# 03_CORE_BOARD.net
KiCad netlist of a schematic drawn in Altium Designer
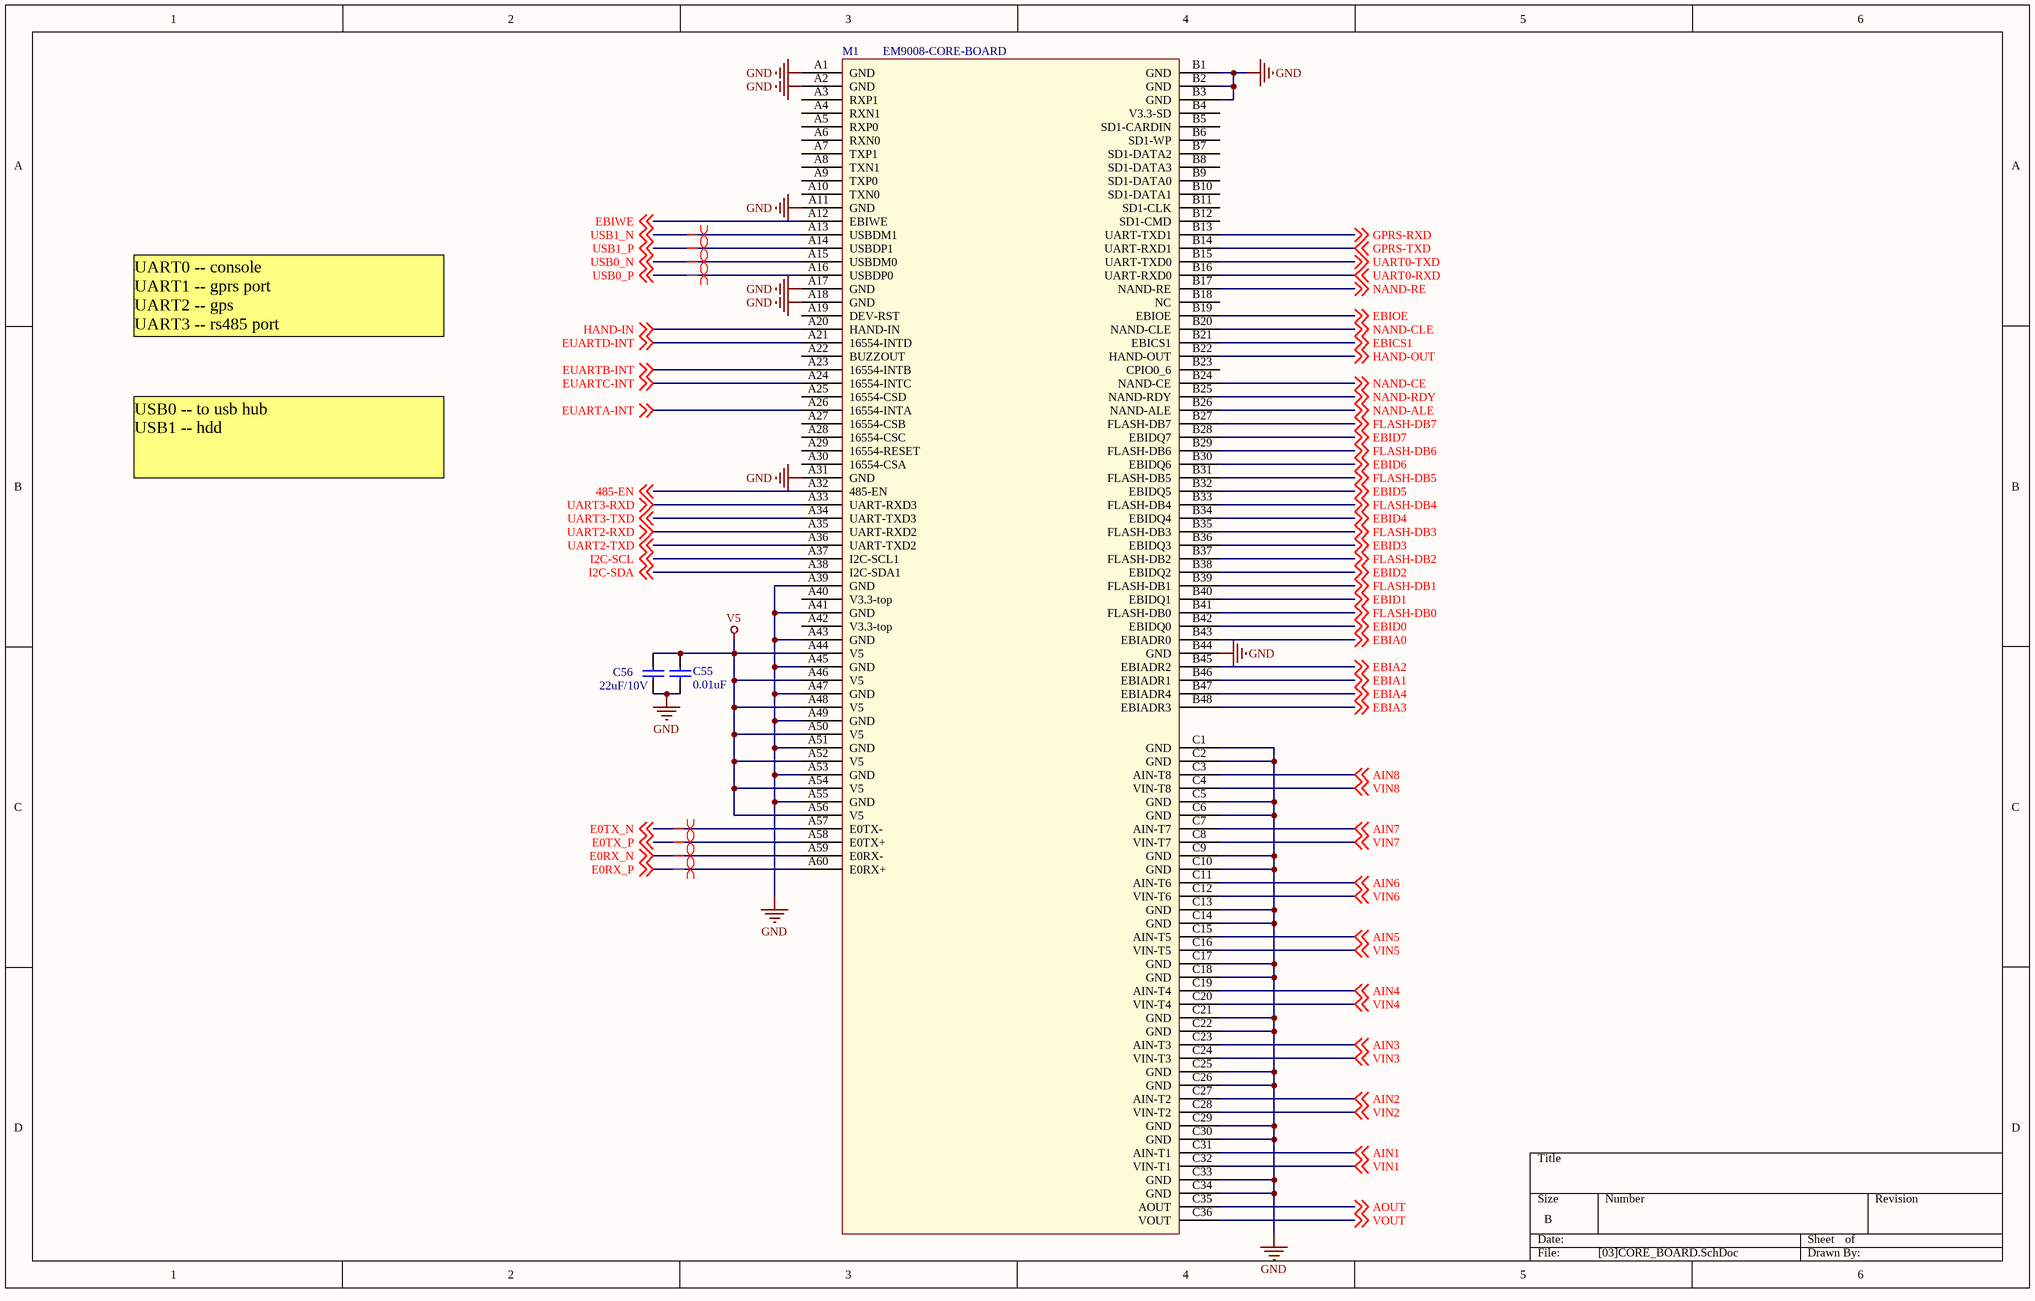
[diagram p0: [03]CORE_BOARD.SchDoc]

(export (version "E")
  (design (tool "Eeschema 10.0.6"))
  (components
    (comp (ref "C55")
      (value "0.01uF")
      (footprint "0603")
      (description "Capacitor")
      (libsource (lib "Miscellaneous Devices") (part "Cap"))
    )
    (comp (ref "C56")
      (value "22uF/10V")
      (footprint "1210")
      (description "Capacitor")
      (libsource (lib "Miscellaneous Devices") (part "Cap"))
    )
    (comp (ref "M1")
      (value "EM9008-CORE-BOARD")
      (footprint "EM9008")
      (libsource (lib "Schlib") (part "EM9008-CORE-BOARD"))
    )
  )
  (nets
    (net (code "1") (name "485-EN") (class "Default")
      (node (ref "M1") (pin "A32") (pinfunction "485-EN_A32") (pintype "passive"))
    )
    (net (code "2") (name "AIN1") (class "Default")
      (node (ref "M1") (pin "C31") (pinfunction "AIN-T1_C31") (pintype "passive"))
    )
    (net (code "3") (name "AIN2") (class "Default")
      (node (ref "M1") (pin "C27") (pinfunction "AIN-T2_C27") (pintype "passive"))
    )
    (net (code "4") (name "AIN3") (class "Default")
      (node (ref "M1") (pin "C23") (pinfunction "AIN-T3_C23") (pintype "passive"))
    )
    (net (code "5") (name "AIN4") (class "Default")
      (node (ref "M1") (pin "C19") (pinfunction "AIN-T4_C19") (pintype "passive"))
    )
    (net (code "6") (name "AIN5") (class "Default")
      (node (ref "M1") (pin "C15") (pinfunction "AIN-T5_C15") (pintype "passive"))
    )
    (net (code "7") (name "AIN6") (class "Default")
      (node (ref "M1") (pin "C11") (pinfunction "AIN-T6_C11") (pintype "passive"))
    )
    (net (code "8") (name "AIN7") (class "Default")
      (node (ref "M1") (pin "C7") (pinfunction "AIN-T7_C7") (pintype "passive"))
    )
    (net (code "9") (name "AIN8") (class "Default")
      (node (ref "M1") (pin "C3") (pinfunction "AIN-T8_C3") (pintype "passive"))
    )
    (net (code "10") (name "AOUT") (class "Default")
      (node (ref "M1") (pin "C35") (pinfunction "AOUT_C35") (pintype "passive"))
    )
    (net (code "11") (name "E0RX_N") (class "Default")
      (node (ref "M1") (pin "A59") (pinfunction "E0RX-_A59") (pintype "passive"))
    )
    (net (code "12") (name "E0RX_P") (class "Default")
      (node (ref "M1") (pin "A60") (pinfunction "E0RX+_A60") (pintype "passive"))
    )
    (net (code "13") (name "E0TX_N") (class "Default")
      (node (ref "M1") (pin "A57") (pinfunction "E0TX-_A57") (pintype "passive"))
    )
    (net (code "14") (name "E0TX_P") (class "Default")
      (node (ref "M1") (pin "A58") (pinfunction "E0TX+_A58") (pintype "passive"))
    )
    (net (code "15") (name "EBIA0") (class "Default")
      (node (ref "M1") (pin "B43") (pinfunction "EBIADR0_B43") (pintype "passive"))
    )
    (net (code "16") (name "EBIA1") (class "Default")
      (node (ref "M1") (pin "B46") (pinfunction "EBIADR1_B46") (pintype "passive"))
    )
    (net (code "17") (name "EBIA2") (class "Default")
      (node (ref "M1") (pin "B45") (pinfunction "EBIADR2_B45") (pintype "passive"))
    )
    (net (code "18") (name "EBIA3") (class "Default")
      (node (ref "M1") (pin "B48") (pinfunction "EBIADR3_B48") (pintype "passive"))
    )
    (net (code "19") (name "EBIA4") (class "Default")
      (node (ref "M1") (pin "B47") (pinfunction "EBIADR4_B47") (pintype "passive"))
    )
    (net (code "20") (name "EBICS1") (class "Default")
      (node (ref "M1") (pin "B21") (pinfunction "EBICS1_B21") (pintype "passive"))
    )
    (net (code "21") (name "EBID0") (class "Default")
      (node (ref "M1") (pin "B42") (pinfunction "EBIDQ0_B42") (pintype "passive"))
    )
    (net (code "22") (name "EBID1") (class "Default")
      (node (ref "M1") (pin "B40") (pinfunction "EBIDQ1_B40") (pintype "passive"))
    )
    (net (code "23") (name "EBID2") (class "Default")
      (node (ref "M1") (pin "B38") (pinfunction "EBIDQ2_B38") (pintype "passive"))
    )
    (net (code "24") (name "EBID3") (class "Default")
      (node (ref "M1") (pin "B36") (pinfunction "EBIDQ3_B36") (pintype "passive"))
    )
    (net (code "25") (name "EBID4") (class "Default")
      (node (ref "M1") (pin "B34") (pinfunction "EBIDQ4_B34") (pintype "passive"))
    )
    (net (code "26") (name "EBID5") (class "Default")
      (node (ref "M1") (pin "B32") (pinfunction "EBIDQ5_B32") (pintype "passive"))
    )
    (net (code "27") (name "EBID6") (class "Default")
      (node (ref "M1") (pin "B30") (pinfunction "EBIDQ6_B30") (pintype "passive"))
    )
    (net (code "28") (name "EBID7") (class "Default")
      (node (ref "M1") (pin "B28") (pinfunction "EBIDQ7_B28") (pintype "passive"))
    )
    (net (code "29") (name "EBIOE") (class "Default")
      (node (ref "M1") (pin "B19") (pinfunction "EBIOE_B19") (pintype "passive"))
    )
    (net (code "30") (name "EBIWE") (class "Default")
      (node (ref "M1") (pin "A12") (pinfunction "EBIWE_A12") (pintype "passive"))
    )
    (net (code "31") (name "EUARTA-INT") (class "Default")
      (node (ref "M1") (pin "A26") (pinfunction "16554-INTA_A26") (pintype "passive"))
    )
    (net (code "32") (name "EUARTB-INT") (class "Default")
      (node (ref "M1") (pin "A23") (pinfunction "16554-INTB_A23") (pintype "passive"))
    )
    (net (code "33") (name "EUARTC-INT") (class "Default")
      (node (ref "M1") (pin "A24") (pinfunction "16554-INTC_A24") (pintype "passive"))
    )
    (net (code "34") (name "EUARTD-INT") (class "Default")
      (node (ref "M1") (pin "A21") (pinfunction "16554-INTD_A21") (pintype "passive"))
    )
    (net (code "35") (name "FLASH-DB0") (class "Default")
      (node (ref "M1") (pin "B41") (pinfunction "FLASH-DB0_B41") (pintype "passive"))
    )
    (net (code "36") (name "FLASH-DB1") (class "Default")
      (node (ref "M1") (pin "B39") (pinfunction "FLASH-DB1_B39") (pintype "passive"))
    )
    (net (code "37") (name "FLASH-DB2") (class "Default")
      (node (ref "M1") (pin "B37") (pinfunction "FLASH-DB2_B37") (pintype "passive"))
    )
    (net (code "38") (name "FLASH-DB3") (class "Default")
      (node (ref "M1") (pin "B35") (pinfunction "FLASH-DB3_B35") (pintype "passive"))
    )
    (net (code "39") (name "FLASH-DB4") (class "Default")
      (node (ref "M1") (pin "B33") (pinfunction "FLASH-DB4_B33") (pintype "passive"))
    )
    (net (code "40") (name "FLASH-DB5") (class "Default")
      (node (ref "M1") (pin "B31") (pinfunction "FLASH-DB5_B31") (pintype "passive"))
    )
    (net (code "41") (name "FLASH-DB6") (class "Default")
      (node (ref "M1") (pin "B29") (pinfunction "FLASH-DB6_B29") (pintype "passive"))
    )
    (net (code "42") (name "FLASH-DB7") (class "Default")
      (node (ref "M1") (pin "B27") (pinfunction "FLASH-DB7_B27") (pintype "passive"))
    )
    (net (code "43") (name "GND") (class "Default")
      (node (ref "C55") (pin "1") (pinfunction "1_1") (pintype "passive"))
      (node (ref "C56") (pin "1") (pinfunction "1_1") (pintype "passive"))
      (node (ref "M1") (pin "A1") (pinfunction "GND_A1") (pintype "passive"))
      (node (ref "M1") (pin "A11") (pinfunction "GND_A11") (pintype "passive"))
      (node (ref "M1") (pin "A17") (pinfunction "GND_A17") (pintype "passive"))
      (node (ref "M1") (pin "A18") (pinfunction "GND_A18") (pintype "passive"))
      (node (ref "M1") (pin "A2") (pinfunction "GND_A2") (pintype "passive"))
      (node (ref "M1") (pin "A31") (pinfunction "GND_A31") (pintype "passive"))
      (node (ref "M1") (pin "A39") (pinfunction "GND_A39") (pintype "passive"))
      (node (ref "M1") (pin "A41") (pinfunction "GND_A41") (pintype "passive"))
      (node (ref "M1") (pin "A43") (pinfunction "GND_A43") (pintype "passive"))
      (node (ref "M1") (pin "A45") (pinfunction "GND_A45") (pintype "passive"))
      (node (ref "M1") (pin "A47") (pinfunction "GND_A47") (pintype "passive"))
      (node (ref "M1") (pin "A49") (pinfunction "GND_A49") (pintype "passive"))
      (node (ref "M1") (pin "A51") (pinfunction "GND_A51") (pintype "passive"))
      (node (ref "M1") (pin "A53") (pinfunction "GND_A53") (pintype "passive"))
      (node (ref "M1") (pin "A55") (pinfunction "GND_A55") (pintype "passive"))
      (node (ref "M1") (pin "B1") (pinfunction "GND_B1") (pintype "passive"))
      (node (ref "M1") (pin "B2") (pinfunction "GND_B2") (pintype "passive"))
      (node (ref "M1") (pin "B3") (pinfunction "GND_B3") (pintype "passive"))
      (node (ref "M1") (pin "B44") (pinfunction "GND_B44") (pintype "passive"))
      (node (ref "M1") (pin "C1") (pinfunction "GND_C1") (pintype "passive"))
      (node (ref "M1") (pin "C10") (pinfunction "GND_C10") (pintype "passive"))
      (node (ref "M1") (pin "C13") (pinfunction "GND_C13") (pintype "passive"))
      (node (ref "M1") (pin "C14") (pinfunction "GND_C14") (pintype "passive"))
      (node (ref "M1") (pin "C17") (pinfunction "GND_C17") (pintype "passive"))
      (node (ref "M1") (pin "C18") (pinfunction "GND_C18") (pintype "passive"))
      (node (ref "M1") (pin "C2") (pinfunction "GND_C2") (pintype "passive"))
      (node (ref "M1") (pin "C21") (pinfunction "GND_C21") (pintype "passive"))
      (node (ref "M1") (pin "C22") (pinfunction "GND_C22") (pintype "passive"))
      (node (ref "M1") (pin "C25") (pinfunction "GND_C25") (pintype "passive"))
      (node (ref "M1") (pin "C26") (pinfunction "GND_C26") (pintype "passive"))
      (node (ref "M1") (pin "C29") (pinfunction "GND_C29") (pintype "passive"))
      (node (ref "M1") (pin "C30") (pinfunction "GND_C30") (pintype "passive"))
      (node (ref "M1") (pin "C33") (pinfunction "GND_C33") (pintype "passive"))
      (node (ref "M1") (pin "C34") (pinfunction "GND_C34") (pintype "passive"))
      (node (ref "M1") (pin "C5") (pinfunction "GND_C5") (pintype "passive"))
      (node (ref "M1") (pin "C6") (pinfunction "GND_C6") (pintype "passive"))
      (node (ref "M1") (pin "C9") (pinfunction "GND_C9") (pintype "passive"))
    )
    (net (code "44") (name "GPRS-RXD") (class "Default")
      (node (ref "M1") (pin "B13") (pinfunction "UART-TXD1_B13") (pintype "passive"))
    )
    (net (code "45") (name "GPRS-TXD") (class "Default")
      (node (ref "M1") (pin "B14") (pinfunction "UART-RXD1_B14") (pintype "passive"))
    )
    (net (code "46") (name "HAND-IN") (class "Default")
      (node (ref "M1") (pin "A20") (pinfunction "HAND-IN_A20") (pintype "passive"))
    )
    (net (code "47") (name "HAND-OUT") (class "Default")
      (node (ref "M1") (pin "B22") (pinfunction "HAND-OUT_B22") (pintype "passive"))
    )
    (net (code "48") (name "I2C-SCL") (class "Default")
      (node (ref "M1") (pin "A37") (pinfunction "I2C-SCL1_A37") (pintype "passive"))
    )
    (net (code "49") (name "I2C-SDA") (class "Default")
      (node (ref "M1") (pin "A38") (pinfunction "I2C-SDA1_A38") (pintype "passive"))
    )
    (net (code "50") (name "NAND-ALE") (class "Default")
      (node (ref "M1") (pin "B26") (pinfunction "NAND-ALE_B26") (pintype "passive"))
    )
    (net (code "51") (name "NAND-CE") (class "Default")
      (node (ref "M1") (pin "B24") (pinfunction "NAND-CE_B24") (pintype "passive"))
    )
    (net (code "52") (name "NAND-CLE") (class "Default")
      (node (ref "M1") (pin "B20") (pinfunction "NAND-CLE_B20") (pintype "passive"))
    )
    (net (code "53") (name "NAND-RDY") (class "Default")
      (node (ref "M1") (pin "B25") (pinfunction "NAND-RDY_B25") (pintype "passive"))
    )
    (net (code "54") (name "NAND-RE") (class "Default")
      (node (ref "M1") (pin "B17") (pinfunction "NAND-RE_B17") (pintype "passive"))
    )
    (net (code "55") (name "UART0-RXD") (class "Default")
      (node (ref "M1") (pin "B16") (pinfunction "UART-RXD0_B16") (pintype "passive"))
    )
    (net (code "56") (name "UART0-TXD") (class "Default")
      (node (ref "M1") (pin "B15") (pinfunction "UART-TXD0_B15") (pintype "passive"))
    )
    (net (code "57") (name "UART2-RXD") (class "Default")
      (node (ref "M1") (pin "A35") (pinfunction "UART-RXD2_A35") (pintype "passive"))
    )
    (net (code "58") (name "UART2-TXD") (class "Default")
      (node (ref "M1") (pin "A36") (pinfunction "UART-TXD2_A36") (pintype "passive"))
    )
    (net (code "59") (name "UART3-RXD") (class "Default")
      (node (ref "M1") (pin "A33") (pinfunction "UART-RXD3_A33") (pintype "passive"))
    )
    (net (code "60") (name "UART3-TXD") (class "Default")
      (node (ref "M1") (pin "A34") (pinfunction "UART-TXD3_A34") (pintype "passive"))
    )
    (net (code "61") (name "USB0_N") (class "Default")
      (node (ref "M1") (pin "A15") (pinfunction "USBDM0_A15") (pintype "passive"))
    )
    (net (code "62") (name "USB0_P") (class "Default")
      (node (ref "M1") (pin "A16") (pinfunction "USBDP0_A16") (pintype "passive"))
    )
    (net (code "63") (name "USB1_N") (class "Default")
      (node (ref "M1") (pin "A13") (pinfunction "USBDM1_A13") (pintype "passive"))
    )
    (net (code "64") (name "USB1_P") (class "Default")
      (node (ref "M1") (pin "A14") (pinfunction "USBDP1_A14") (pintype "passive"))
    )
    (net (code "65") (name "V5") (class "Default")
      (node (ref "C55") (pin "2") (pinfunction "2_2") (pintype "passive"))
      (node (ref "C56") (pin "2") (pinfunction "2_2") (pintype "passive"))
      (node (ref "M1") (pin "A44") (pinfunction "V5_A44") (pintype "passive"))
      (node (ref "M1") (pin "A46") (pinfunction "V5_A46") (pintype "passive"))
      (node (ref "M1") (pin "A48") (pinfunction "V5_A48") (pintype "passive"))
      (node (ref "M1") (pin "A50") (pinfunction "V5_A50") (pintype "passive"))
      (node (ref "M1") (pin "A52") (pinfunction "V5_A52") (pintype "passive"))
      (node (ref "M1") (pin "A54") (pinfunction "V5_A54") (pintype "passive"))
      (node (ref "M1") (pin "A56") (pinfunction "V5_A56") (pintype "passive"))
    )
    (net (code "66") (name "VIN1") (class "Default")
      (node (ref "M1") (pin "C32") (pinfunction "VIN-T1_C32") (pintype "passive"))
    )
    (net (code "67") (name "VIN2") (class "Default")
      (node (ref "M1") (pin "C28") (pinfunction "VIN-T2_C28") (pintype "passive"))
    )
    (net (code "68") (name "VIN3") (class "Default")
      (node (ref "M1") (pin "C24") (pinfunction "VIN-T3_C24") (pintype "passive"))
    )
    (net (code "69") (name "VIN4") (class "Default")
      (node (ref "M1") (pin "C20") (pinfunction "VIN-T4_C20") (pintype "passive"))
    )
    (net (code "70") (name "VIN5") (class "Default")
      (node (ref "M1") (pin "C16") (pinfunction "VIN-T5_C16") (pintype "passive"))
    )
    (net (code "71") (name "VIN6") (class "Default")
      (node (ref "M1") (pin "C12") (pinfunction "VIN-T6_C12") (pintype "passive"))
    )
    (net (code "72") (name "VIN7") (class "Default")
      (node (ref "M1") (pin "C8") (pinfunction "VIN-T7_C8") (pintype "passive"))
    )
    (net (code "73") (name "VIN8") (class "Default")
      (node (ref "M1") (pin "C4") (pinfunction "VIN-T8_C4") (pintype "passive"))
    )
    (net (code "74") (name "VOUT") (class "Default")
      (node (ref "M1") (pin "C36") (pinfunction "VOUT_C36") (pintype "passive"))
    )
    (net (code "75") (name "unconnected-(M1-16554-CSA-PadA30)") (class "Default")
      (node (ref "M1") (pin "A30") (pinfunction "16554-CSA_A30") (pintype "passive"))
    )
    (net (code "76") (name "unconnected-(M1-16554-CSB-PadA27)") (class "Default")
      (node (ref "M1") (pin "A27") (pinfunction "16554-CSB_A27") (pintype "passive"))
    )
    (net (code "77") (name "unconnected-(M1-16554-CSC-PadA28)") (class "Default")
      (node (ref "M1") (pin "A28") (pinfunction "16554-CSC_A28") (pintype "passive"))
    )
    (net (code "78") (name "unconnected-(M1-16554-CSD-PadA25)") (class "Default")
      (node (ref "M1") (pin "A25") (pinfunction "16554-CSD_A25") (pintype "passive"))
    )
    (net (code "79") (name "unconnected-(M1-16554-RESET-PadA29)") (class "Default")
      (node (ref "M1") (pin "A29") (pinfunction "16554-RESET_A29") (pintype "passive"))
    )
    (net (code "80") (name "unconnected-(M1-BUZZOUT-PadA22)") (class "Default")
      (node (ref "M1") (pin "A22") (pinfunction "BUZZOUT_A22") (pintype "passive"))
    )
    (net (code "81") (name "unconnected-(M1-CPIO0_6-PadB23)") (class "Default")
      (node (ref "M1") (pin "B23") (pinfunction "CPIO0_6_B23") (pintype "passive"))
    )
    (net (code "82") (name "unconnected-(M1-DEV-RST-PadA19)") (class "Default")
      (node (ref "M1") (pin "A19") (pinfunction "DEV-RST_A19") (pintype "passive"))
    )
    (net (code "83") (name "unconnected-(M1-NC-PadB18)") (class "Default")
      (node (ref "M1") (pin "B18") (pinfunction "NC_B18") (pintype "passive"))
    )
    (net (code "84") (name "unconnected-(M1-RXN0-PadA6)") (class "Default")
      (node (ref "M1") (pin "A6") (pinfunction "RXN0_A6") (pintype "passive"))
    )
    (net (code "85") (name "unconnected-(M1-RXN1-PadA4)") (class "Default")
      (node (ref "M1") (pin "A4") (pinfunction "RXN1_A4") (pintype "passive"))
    )
    (net (code "86") (name "unconnected-(M1-RXP0-PadA5)") (class "Default")
      (node (ref "M1") (pin "A5") (pinfunction "RXP0_A5") (pintype "passive"))
    )
    (net (code "87") (name "unconnected-(M1-RXP1-PadA3)") (class "Default")
      (node (ref "M1") (pin "A3") (pinfunction "RXP1_A3") (pintype "passive"))
    )
    (net (code "88") (name "unconnected-(M1-SD1-CARDIN-PadB5)") (class "Default")
      (node (ref "M1") (pin "B5") (pinfunction "SD1-CARDIN_B5") (pintype "passive"))
    )
    (net (code "89") (name "unconnected-(M1-SD1-CLK-PadB11)") (class "Default")
      (node (ref "M1") (pin "B11") (pinfunction "SD1-CLK_B11") (pintype "passive"))
    )
    (net (code "90") (name "unconnected-(M1-SD1-CMD-PadB12)") (class "Default")
      (node (ref "M1") (pin "B12") (pinfunction "SD1-CMD_B12") (pintype "passive"))
    )
    (net (code "91") (name "unconnected-(M1-SD1-DATA0-PadB9)") (class "Default")
      (node (ref "M1") (pin "B9") (pinfunction "SD1-DATA0_B9") (pintype "passive"))
    )
    (net (code "92") (name "unconnected-(M1-SD1-DATA1-PadB10)") (class "Default")
      (node (ref "M1") (pin "B10") (pinfunction "SD1-DATA1_B10") (pintype "passive"))
    )
    (net (code "93") (name "unconnected-(M1-SD1-DATA2-PadB7)") (class "Default")
      (node (ref "M1") (pin "B7") (pinfunction "SD1-DATA2_B7") (pintype "passive"))
    )
    (net (code "94") (name "unconnected-(M1-SD1-DATA3-PadB8)") (class "Default")
      (node (ref "M1") (pin "B8") (pinfunction "SD1-DATA3_B8") (pintype "passive"))
    )
    (net (code "95") (name "unconnected-(M1-SD1-WP-PadB6)") (class "Default")
      (node (ref "M1") (pin "B6") (pinfunction "SD1-WP_B6") (pintype "passive"))
    )
    (net (code "96") (name "unconnected-(M1-TXN0-PadA10)") (class "Default")
      (node (ref "M1") (pin "A10") (pinfunction "TXN0_A10") (pintype "passive"))
    )
    (net (code "97") (name "unconnected-(M1-TXN1-PadA8)") (class "Default")
      (node (ref "M1") (pin "A8") (pinfunction "TXN1_A8") (pintype "passive"))
    )
    (net (code "98") (name "unconnected-(M1-TXP0-PadA9)") (class "Default")
      (node (ref "M1") (pin "A9") (pinfunction "TXP0_A9") (pintype "passive"))
    )
    (net (code "99") (name "unconnected-(M1-TXP1-PadA7)") (class "Default")
      (node (ref "M1") (pin "A7") (pinfunction "TXP1_A7") (pintype "passive"))
    )
    (net (code "100") (name "unconnected-(M1-V3.3-SD-PadB4)") (class "Default")
      (node (ref "M1") (pin "B4") (pinfunction "V3.3-SD_B4") (pintype "passive"))
    )
    (net (code "101") (name "unconnected-(M1-V3.3-top-PadA40)") (class "Default")
      (node (ref "M1") (pin "A40") (pinfunction "V3.3-top_A40") (pintype "passive"))
    )
    (net (code "102") (name "unconnected-(M1-V3.3-top-PadA42)") (class "Default")
      (node (ref "M1") (pin "A42") (pinfunction "V3.3-top_A42") (pintype "passive"))
    )
  )
)
